# To-mate-Oh.net
KiCad netlist of a schematic drawn in EAGLE
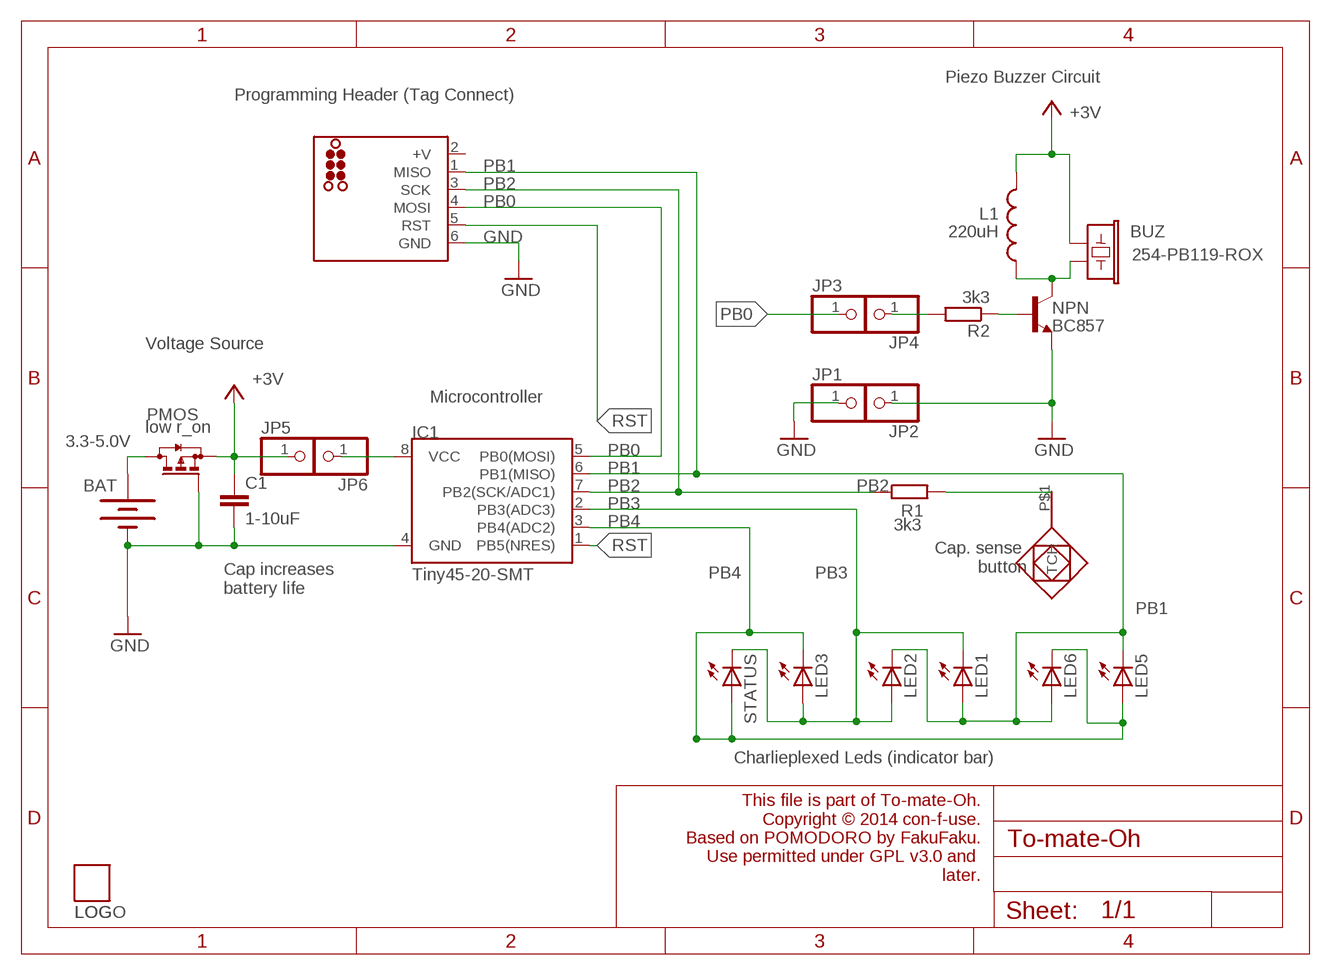
[diagram p0: schematic, sheet 1]

(export (version "E")
  (design (tool "Eeschema 10.0.6"))
  (components
    (comp (ref "BAT")
      (value "3.3-5.0V")
      (footprint "eagle-import:BATTERY_20MM_PTH_COMPACT")
      (libsource (lib "eagle-import") (part "BATTERYFOB"))
    )
    (comp (ref "BUZ")
      (value "254-PB119-ROX")
      (footprint "eagle-import:BUZZER-CMT1102")
      (libsource (lib "eagle-import") (part "BUZZERSMD3"))
    )
    (comp (ref "C1")
      (value "1-10uF")
      (footprint "eagle-import:C1210")
      (libsource (lib "eagle-import") (part "C-EUC1210"))
    )
    (comp (ref "CAP_SENSE")
      (value "PAD")
      (footprint "eagle-import:EMPTY")
      (libsource (lib "eagle-import") (part "PAD"))
    )
    (comp (ref "IC1")
      (value "Tiny45-20-SMT")
      (footprint "eagle-import:SO08-EIAJ")
      (libsource (lib "eagle-import") (part "ATTINY45TINY45-20-SMT"))
    )
    (comp (ref "ISP")
      (value "ATMEL-ISPATMEL_ISP_TC2030")
      (footprint "eagle-import:TC2030-MCP-NL")
      (libsource (lib "eagle-import") (part "ATMEL-ISPATMEL_ISP_TC2030"))
    )
    (comp (ref "JP1")
      (value "JGND1")
      (footprint "eagle-import:1X01")
      (libsource (lib "eagle-import") (part "PINHD-1X1"))
    )
    (comp (ref "JP2")
      (value "JGND2")
      (footprint "eagle-import:1X01")
      (libsource (lib "eagle-import") (part "PINHD-1X1"))
    )
    (comp (ref "JP3")
      (value "JPB1")
      (footprint "eagle-import:1X01")
      (libsource (lib "eagle-import") (part "PINHD-1X1"))
    )
    (comp (ref "JP4")
      (value "JPB2")
      (footprint "eagle-import:1X01")
      (libsource (lib "eagle-import") (part "PINHD-1X1"))
    )
    (comp (ref "JP5")
      (value "JVCC1")
      (footprint "eagle-import:1X01")
      (libsource (lib "eagle-import") (part "PINHD-1X1"))
    )
    (comp (ref "JP6")
      (value "JVCC2")
      (footprint "eagle-import:1X01")
      (libsource (lib "eagle-import") (part "PINHD-1X1"))
    )
    (comp (ref "L1")
      (value "220uH")
      (footprint "eagle-import:1007")
      (libsource (lib "eagle-import") (part "INDUCTOR1007"))
    )
    (comp (ref "LED1")
      (value "Blue")
      (footprint "eagle-import:CHIPLED_0805")
      (libsource (lib "eagle-import") (part "LEDCHIPLED_0805"))
    )
    (comp (ref "LED2")
      (value "Blue")
      (footprint "eagle-import:CHIPLED_0805")
      (libsource (lib "eagle-import") (part "LEDCHIPLED_0805"))
    )
    (comp (ref "LED3")
      (value "Blue")
      (footprint "eagle-import:CHIPLED_0805")
      (libsource (lib "eagle-import") (part "LEDCHIPLED_0805"))
    )
    (comp (ref "LED5")
      (value "Blue")
      (footprint "eagle-import:CHIPLED_0805")
      (libsource (lib "eagle-import") (part "LEDCHIPLED_0805"))
    )
    (comp (ref "LED6")
      (value "Blue")
      (footprint "eagle-import:CHIPLED_0805")
      (libsource (lib "eagle-import") (part "LEDCHIPLED_0805"))
    )
    (comp (ref "LOG")
      (value "UNETHILOGO")
      (footprint "eagle-import:UNETHILOGO_TINY_SILK")
      (libsource (lib "eagle-import") (part "UNETHILOGO"))
    )
    (comp (ref "LOGO")
      (value "UNETHILOGOUNETHILOGO_TINY")
      (footprint "eagle-import:UNETHILOGO_TINY")
      (libsource (lib "eagle-import") (part "UNETHILOGOUNETHILOGO_TINY"))
    )
    (comp (ref "NPN")
      (value "BC857")
      (footprint "eagle-import:SOT23-BEC")
      (libsource (lib "eagle-import") (part "-NPN-SOT23-BECBC849"))
    )
    (comp (ref "PMOS")
      (value "low r_on")
      (footprint "eagle-import:SOT23")
      (libsource (lib "eagle-import") (part "BSS84"))
    )
    (comp (ref "R1")
      (value "3k3")
      (footprint "eagle-import:R0805")
      (libsource (lib "eagle-import") (part "R-EU_R0805"))
    )
    (comp (ref "R2")
      (value "3k3")
      (footprint "eagle-import:R0805")
      (libsource (lib "eagle-import") (part "R-EU_R0805"))
    )
    (comp (ref "STATUS")
      (value "Red")
      (footprint "eagle-import:CHIPLED_0805")
      (libsource (lib "eagle-import") (part "LEDCHIPLED_0805"))
    )
  )
  (nets
    (net (code "1") (name "+3V") (class "Default")
      (node (ref "BUZ") (pin "1") (pinfunction "1_1") (pintype "passive"))
      (node (ref "C1") (pin "1") (pinfunction "1_1") (pintype "passive"))
      (node (ref "JP5") (pin "1") (pinfunction "1_1") (pintype "passive"))
      (node (ref "L1") (pin "2") (pinfunction "2_2") (pintype "passive"))
      (node (ref "PMOS") (pin "2") (pinfunction "S_2") (pintype "passive"))
    )
    (net (code "2") (name "/+V") (class "Default")
      (node (ref "ISP") (pin "2") (pinfunction "+V_2") (pintype "power_in"))
    )
    (net (code "3") (name "/PB1") (class "Default")
      (node (ref "IC1") (pin "6") (pinfunction "PB1(MISO)_6") (pintype "bidirectional"))
      (node (ref "ISP") (pin "1") (pinfunction "MISO_1") (pintype "input"))
      (node (ref "LED1") (pin "A") (pinfunction "A_A") (pintype "passive"))
      (node (ref "LED2") (pin "C") (pinfunction "C_C") (pintype "passive"))
      (node (ref "LED5") (pin "C") (pinfunction "C_C") (pintype "passive"))
      (node (ref "LED6") (pin "A") (pinfunction "A_A") (pintype "passive"))
    )
    (net (code "4") (name "/PB2") (class "Default")
      (node (ref "IC1") (pin "7") (pinfunction "PB2(SCK/ADC1)_7") (pintype "bidirectional"))
      (node (ref "ISP") (pin "3") (pinfunction "SCK_3") (pintype "output"))
      (node (ref "R1") (pin "1") (pinfunction "1_1") (pintype "passive"))
    )
    (net (code "5") (name "/PB3") (class "Default")
      (node (ref "IC1") (pin "2") (pinfunction "PB3(ADC3)_2") (pintype "bidirectional"))
      (node (ref "LED1") (pin "C") (pinfunction "C_C") (pintype "passive"))
      (node (ref "LED2") (pin "A") (pinfunction "A_A") (pintype "passive"))
      (node (ref "LED3") (pin "A") (pinfunction "A_A") (pintype "passive"))
      (node (ref "STATUS") (pin "C") (pinfunction "C_C") (pintype "passive"))
    )
    (net (code "6") (name "/PB4") (class "Default")
      (node (ref "IC1") (pin "3") (pinfunction "PB4(ADC2)_3") (pintype "bidirectional"))
      (node (ref "LED3") (pin "C") (pinfunction "C_C") (pintype "passive"))
      (node (ref "LED5") (pin "A") (pinfunction "A_A") (pintype "passive"))
      (node (ref "LED6") (pin "C") (pinfunction "C_C") (pintype "passive"))
      (node (ref "STATUS") (pin "A") (pinfunction "A_A") (pintype "passive"))
    )
    (net (code "7") (name "GND") (class "Default")
      (node (ref "BAT") (pin "2") (pinfunction "-_2") (pintype "power_in"))
      (node (ref "C1") (pin "2") (pinfunction "2_2") (pintype "passive"))
      (node (ref "IC1") (pin "4") (pinfunction "GND_4") (pintype "bidirectional"))
      (node (ref "ISP") (pin "6") (pinfunction "GND_6") (pintype "power_in"))
      (node (ref "JP1") (pin "1") (pinfunction "1_1") (pintype "passive"))
      (node (ref "JP2") (pin "1") (pinfunction "1_1") (pintype "passive"))
      (node (ref "NPN") (pin "E") (pinfunction "E_E") (pintype "passive"))
      (node (ref "PMOS") (pin "1") (pinfunction "G_1") (pintype "passive"))
    )
    (net (code "8") (name "Net-(BUZ-Pad2)") (class "Default")
      (node (ref "BUZ") (pin "2") (pinfunction "2_2") (pintype "passive"))
      (node (ref "L1") (pin "1") (pinfunction "1_1") (pintype "passive"))
      (node (ref "NPN") (pin "C") (pinfunction "C_C") (pintype "passive"))
    )
    (net (code "9") (name "Net-(CAP_SENSE-TCH)") (class "Default")
      (node (ref "CAP_SENSE") (pin "P$1") (pinfunction "TCH_P$1") (pintype "bidirectional"))
      (node (ref "R1") (pin "2") (pinfunction "2_2") (pintype "passive"))
    )
    (net (code "10") (name "Net-(IC1-VCC)") (class "Default")
      (node (ref "IC1") (pin "8") (pinfunction "VCC_8") (pintype "bidirectional"))
      (node (ref "JP6") (pin "1") (pinfunction "1_1") (pintype "passive"))
    )
    (net (code "11") (name "Net-(JP4-Pad1)") (class "Default")
      (node (ref "JP4") (pin "1") (pinfunction "1_1") (pintype "passive"))
      (node (ref "R2") (pin "2") (pinfunction "2_2") (pintype "passive"))
    )
    (net (code "12") (name "Net-(NPN-PadB)") (class "Default")
      (node (ref "NPN") (pin "B") (pinfunction "B_B") (pintype "passive"))
      (node (ref "R2") (pin "1") (pinfunction "1_1") (pintype "passive"))
    )
    (net (code "13") (name "Net-(PMOS-D)") (class "Default")
      (node (ref "BAT") (pin "1") (pinfunction "+_1") (pintype "power_in"))
      (node (ref "BAT") (pin "1@2") (pinfunction "+_1@2") (pintype "power_in"))
      (node (ref "PMOS") (pin "3") (pinfunction "D_3") (pintype "passive"))
    )
    (net (code "14") (name "PB0") (class "Default")
      (node (ref "IC1") (pin "5") (pinfunction "PB0(MOSI)_5") (pintype "bidirectional"))
      (node (ref "ISP") (pin "4") (pinfunction "MOSI_4") (pintype "output"))
      (node (ref "JP3") (pin "1") (pinfunction "1_1") (pintype "passive"))
    )
    (net (code "15") (name "RST") (class "Default")
      (node (ref "IC1") (pin "1") (pinfunction "PB5(NRES)_1") (pintype "bidirectional"))
      (node (ref "ISP") (pin "5") (pinfunction "RST_5") (pintype "output"))
    )
  )
)
